# Headphone_Amplifier_Fixed.net
KiCad netlist of a schematic drawn in EAGLE
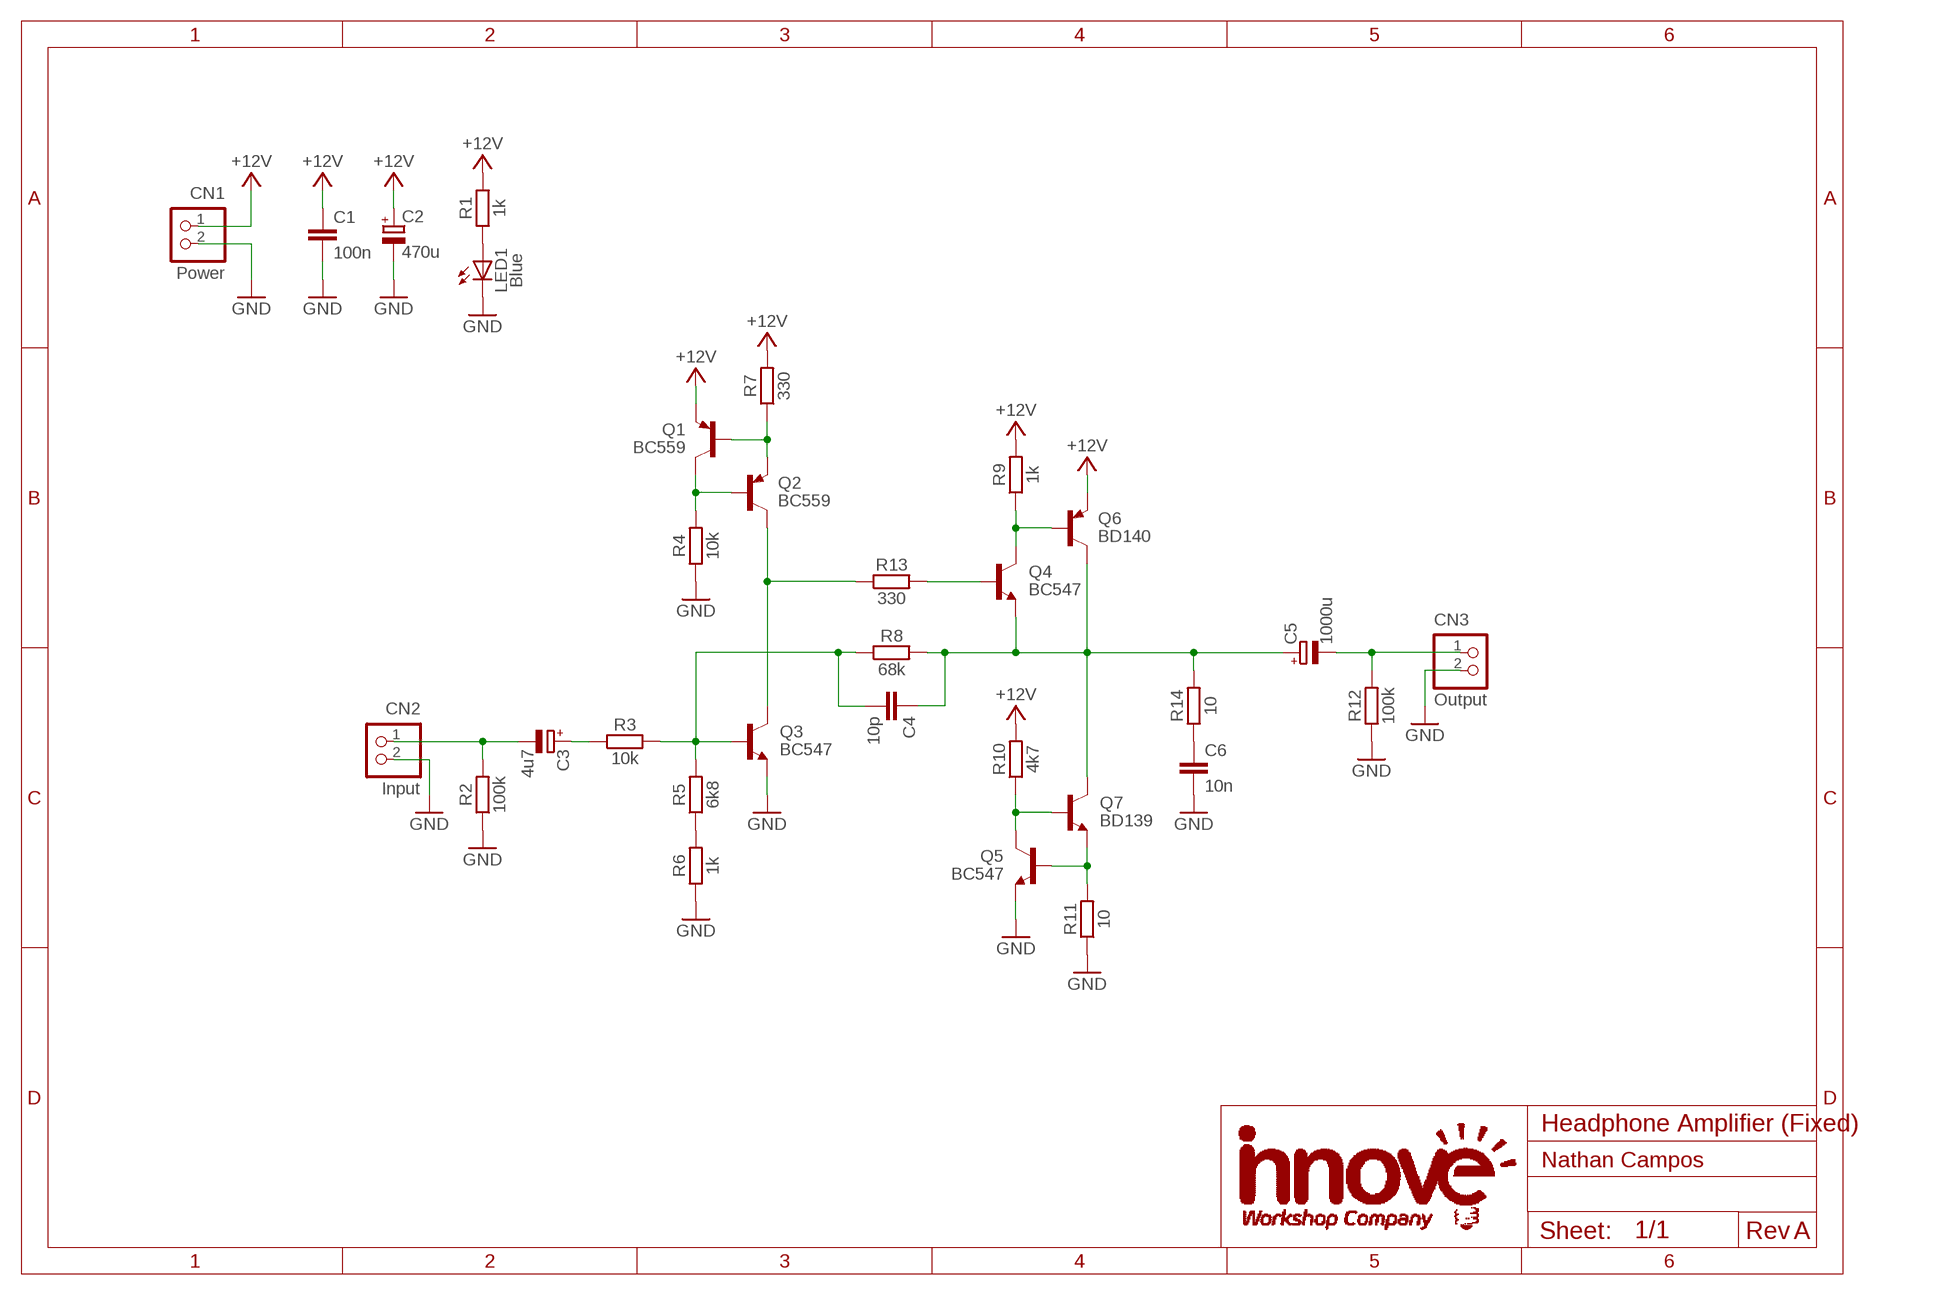
[diagram p0: schematic, sheet 1]

(export (version "E")
  (design (tool "Eeschema 10.0.6"))
  (components
    (comp (ref "C1")
      (value "100n")
      (footprint "eagle-import:C050-025X075")
      (libsource (lib "eagle-import") (part "C5.0-2.5X7.5"))
    )
    (comp (ref "C2")
      (value "470u")
      (footprint "eagle-import:E5-10")
      (libsource (lib "eagle-import") (part "CPOL-E5-10"))
    )
    (comp (ref "C3")
      (value "4u7")
      (footprint "eagle-import:E1,8-4")
      (libsource (lib "eagle-import") (part "CPOL-E1.8-4"))
    )
    (comp (ref "C4")
      (value "10p")
      (footprint "eagle-import:C050-025X075")
      (libsource (lib "eagle-import") (part "C5.0-2.5X7.5"))
    )
    (comp (ref "C5")
      (value "1000u")
      (footprint "eagle-import:E5-10")
      (libsource (lib "eagle-import") (part "CPOL-E5-10"))
    )
    (comp (ref "C6")
      (value "10n")
      (footprint "eagle-import:C050-025X075")
      (libsource (lib "eagle-import") (part "C5.0-2.5X7.5"))
    )
    (comp (ref "CN1")
      (value "Power")
      (footprint "eagle-import:B2B-XH-A")
      (libsource (lib "eagle-import") (part "B2B-XH-A"))
    )
    (comp (ref "CN2")
      (value "Input")
      (footprint "eagle-import:B2B-XH-A")
      (libsource (lib "eagle-import") (part "B2B-XH-A"))
    )
    (comp (ref "CN3")
      (value "Output")
      (footprint "eagle-import:B2B-XH-A")
      (libsource (lib "eagle-import") (part "B2B-XH-A"))
    )
    (comp (ref "LED1")
      (value "Blue")
      (footprint "eagle-import:LED5MM")
      (libsource (lib "eagle-import") (part "LED5MM"))
    )
    (comp (ref "Q1")
      (value "BC559")
      (footprint "eagle-import:TO92")
      (libsource (lib "eagle-import") (part "BC559"))
    )
    (comp (ref "Q2")
      (value "BC559")
      (footprint "eagle-import:TO92")
      (libsource (lib "eagle-import") (part "BC559"))
    )
    (comp (ref "Q3")
      (value "BC547")
      (footprint "eagle-import:TO92")
      (libsource (lib "eagle-import") (part "BC547"))
    )
    (comp (ref "Q4")
      (value "BC547")
      (footprint "eagle-import:TO92")
      (libsource (lib "eagle-import") (part "BC547"))
    )
    (comp (ref "Q5")
      (value "BC547")
      (footprint "eagle-import:TO92")
      (libsource (lib "eagle-import") (part "BC547"))
    )
    (comp (ref "Q6")
      (value "BD140")
      (footprint "eagle-import:TO126V")
      (libsource (lib "eagle-import") (part "BD140"))
    )
    (comp (ref "Q7")
      (value "BD139")
      (footprint "eagle-import:TO126V")
      (libsource (lib "eagle-import") (part "BD139"))
    )
    (comp (ref "R1")
      (value "1k")
      (footprint "eagle-import:0207_10")
      (libsource (lib "eagle-import") (part "RT0207"))
    )
    (comp (ref "R2")
      (value "100k")
      (footprint "eagle-import:0207_10")
      (libsource (lib "eagle-import") (part "RT0207"))
    )
    (comp (ref "R3")
      (value "10k")
      (footprint "eagle-import:0207_10")
      (libsource (lib "eagle-import") (part "RT0207"))
    )
    (comp (ref "R4")
      (value "10k")
      (footprint "eagle-import:0207_10")
      (libsource (lib "eagle-import") (part "RT0207"))
    )
    (comp (ref "R5")
      (value "6k8")
      (footprint "eagle-import:0207_10")
      (libsource (lib "eagle-import") (part "RT0207"))
    )
    (comp (ref "R6")
      (value "1k")
      (footprint "eagle-import:0207_10")
      (libsource (lib "eagle-import") (part "RT0207"))
    )
    (comp (ref "R7")
      (value "330")
      (footprint "eagle-import:0207_10")
      (libsource (lib "eagle-import") (part "RT0207"))
    )
    (comp (ref "R8")
      (value "68k")
      (footprint "eagle-import:0207_10")
      (libsource (lib "eagle-import") (part "RT0207"))
    )
    (comp (ref "R9")
      (value "1k")
      (footprint "eagle-import:0207_10")
      (libsource (lib "eagle-import") (part "RT0207"))
    )
    (comp (ref "R10")
      (value "4k7")
      (footprint "eagle-import:0207_10")
      (libsource (lib "eagle-import") (part "RT0207"))
    )
    (comp (ref "R11")
      (value "10")
      (footprint "eagle-import:0207_10")
      (libsource (lib "eagle-import") (part "RT0207"))
    )
    (comp (ref "R12")
      (value "100k")
      (footprint "eagle-import:0207_10")
      (libsource (lib "eagle-import") (part "RT0207"))
    )
    (comp (ref "R13")
      (value "330")
      (footprint "eagle-import:0207_10")
      (libsource (lib "eagle-import") (part "RT0207"))
    )
    (comp (ref "R14")
      (value "10")
      (footprint "eagle-import:0207_10")
      (libsource (lib "eagle-import") (part "RT0207"))
    )
  )
  (nets
    (net (code "1") (name "+12V") (class "Default")
      (node (ref "C1") (pin "1") (pinfunction "1_1") (pintype "passive"))
      (node (ref "C2") (pin "+") (pinfunction "+_+") (pintype "passive"))
      (node (ref "CN1") (pin "1") (pinfunction "1_1") (pintype "passive"))
      (node (ref "Q1") (pin "3") (pinfunction "E_3") (pintype "passive"))
      (node (ref "Q6") (pin "1") (pinfunction "E_1") (pintype "passive"))
      (node (ref "R1") (pin "2") (pinfunction "2_2") (pintype "passive"))
      (node (ref "R10") (pin "2") (pinfunction "2_2") (pintype "passive"))
      (node (ref "R7") (pin "2") (pinfunction "2_2") (pintype "passive"))
      (node (ref "R9") (pin "2") (pinfunction "2_2") (pintype "passive"))
    )
    (net (code "2") (name "GND") (class "Default")
      (node (ref "C1") (pin "2") (pinfunction "2_2") (pintype "passive"))
      (node (ref "C2") (pin "-") (pinfunction "-_-") (pintype "passive"))
      (node (ref "C6") (pin "2") (pinfunction "2_2") (pintype "passive"))
      (node (ref "CN1") (pin "2") (pinfunction "2_2") (pintype "passive"))
      (node (ref "CN2") (pin "2") (pinfunction "2_2") (pintype "passive"))
      (node (ref "CN3") (pin "2") (pinfunction "2_2") (pintype "passive"))
      (node (ref "LED1") (pin "K") (pinfunction "C_K") (pintype "passive"))
      (node (ref "Q3") (pin "3") (pinfunction "E_3") (pintype "passive"))
      (node (ref "Q5") (pin "3") (pinfunction "E_3") (pintype "passive"))
      (node (ref "R11") (pin "1") (pinfunction "1_1") (pintype "passive"))
      (node (ref "R12") (pin "1") (pinfunction "1_1") (pintype "passive"))
      (node (ref "R2") (pin "1") (pinfunction "1_1") (pintype "passive"))
      (node (ref "R4") (pin "1") (pinfunction "1_1") (pintype "passive"))
      (node (ref "R6") (pin "1") (pinfunction "1_1") (pintype "passive"))
    )
    (net (code "3") (name "Net-(C3-Pad+)") (class "Default")
      (node (ref "C3") (pin "+") (pinfunction "+_+") (pintype "passive"))
      (node (ref "R3") (pin "1") (pinfunction "1_1") (pintype "passive"))
    )
    (net (code "4") (name "Net-(C3-Pad-)") (class "Default")
      (node (ref "C3") (pin "-") (pinfunction "-_-") (pintype "passive"))
      (node (ref "CN2") (pin "1") (pinfunction "1_1") (pintype "passive"))
      (node (ref "R2") (pin "2") (pinfunction "2_2") (pintype "passive"))
    )
    (net (code "5") (name "Net-(C5-Pad-)") (class "Default")
      (node (ref "C5") (pin "-") (pinfunction "-_-") (pintype "passive"))
      (node (ref "CN3") (pin "1") (pinfunction "1_1") (pintype "passive"))
      (node (ref "R12") (pin "2") (pinfunction "2_2") (pintype "passive"))
    )
    (net (code "6") (name "Net-(C6-Pad1)") (class "Default")
      (node (ref "C6") (pin "1") (pinfunction "1_1") (pintype "passive"))
      (node (ref "R14") (pin "1") (pinfunction "1_1") (pintype "passive"))
    )
    (net (code "7") (name "Net-(LED1-PadA)") (class "Default")
      (node (ref "LED1") (pin "A") (pinfunction "A_A") (pintype "passive"))
      (node (ref "R1") (pin "1") (pinfunction "1_1") (pintype "passive"))
    )
    (net (code "8") (name "Net-(Q1-B)") (class "Default")
      (node (ref "Q1") (pin "2") (pinfunction "B_2") (pintype "passive"))
      (node (ref "Q2") (pin "3") (pinfunction "E_3") (pintype "passive"))
      (node (ref "R7") (pin "1") (pinfunction "1_1") (pintype "passive"))
    )
    (net (code "9") (name "Net-(Q1-C)") (class "Default")
      (node (ref "Q1") (pin "1") (pinfunction "C_1") (pintype "passive"))
      (node (ref "Q2") (pin "2") (pinfunction "B_2") (pintype "passive"))
      (node (ref "R4") (pin "2") (pinfunction "2_2") (pintype "passive"))
    )
    (net (code "10") (name "Net-(Q2-C)") (class "Default")
      (node (ref "Q2") (pin "1") (pinfunction "C_1") (pintype "passive"))
      (node (ref "Q3") (pin "1") (pinfunction "C_1") (pintype "passive"))
      (node (ref "R13") (pin "1") (pinfunction "1_1") (pintype "passive"))
    )
    (net (code "11") (name "Net-(Q3-B)") (class "Default")
      (node (ref "C4") (pin "2") (pinfunction "2_2") (pintype "passive"))
      (node (ref "Q3") (pin "2") (pinfunction "B_2") (pintype "passive"))
      (node (ref "R3") (pin "2") (pinfunction "2_2") (pintype "passive"))
      (node (ref "R5") (pin "2") (pinfunction "2_2") (pintype "passive"))
      (node (ref "R8") (pin "1") (pinfunction "1_1") (pintype "passive"))
    )
    (net (code "12") (name "Net-(Q4-B)") (class "Default")
      (node (ref "Q4") (pin "2") (pinfunction "B_2") (pintype "passive"))
      (node (ref "R13") (pin "2") (pinfunction "2_2") (pintype "passive"))
    )
    (net (code "13") (name "Net-(Q4-C)") (class "Default")
      (node (ref "Q4") (pin "1") (pinfunction "C_1") (pintype "passive"))
      (node (ref "Q6") (pin "3") (pinfunction "B_3") (pintype "passive"))
      (node (ref "R9") (pin "1") (pinfunction "1_1") (pintype "passive"))
    )
    (net (code "14") (name "Net-(Q4-E)") (class "Default")
      (node (ref "C4") (pin "1") (pinfunction "1_1") (pintype "passive"))
      (node (ref "C5") (pin "+") (pinfunction "+_+") (pintype "passive"))
      (node (ref "Q4") (pin "3") (pinfunction "E_3") (pintype "passive"))
      (node (ref "Q6") (pin "2") (pinfunction "C_2") (pintype "passive"))
      (node (ref "Q7") (pin "2") (pinfunction "C_2") (pintype "passive"))
      (node (ref "R14") (pin "2") (pinfunction "2_2") (pintype "passive"))
      (node (ref "R8") (pin "2") (pinfunction "2_2") (pintype "passive"))
    )
    (net (code "15") (name "Net-(Q5-B)") (class "Default")
      (node (ref "Q5") (pin "2") (pinfunction "B_2") (pintype "passive"))
      (node (ref "Q7") (pin "1") (pinfunction "E_1") (pintype "passive"))
      (node (ref "R11") (pin "2") (pinfunction "2_2") (pintype "passive"))
    )
    (net (code "16") (name "Net-(Q5-C)") (class "Default")
      (node (ref "Q5") (pin "1") (pinfunction "C_1") (pintype "passive"))
      (node (ref "Q7") (pin "3") (pinfunction "B_3") (pintype "passive"))
      (node (ref "R10") (pin "1") (pinfunction "1_1") (pintype "passive"))
    )
    (net (code "17") (name "Net-(R5-Pad1)") (class "Default")
      (node (ref "R5") (pin "1") (pinfunction "1_1") (pintype "passive"))
      (node (ref "R6") (pin "2") (pinfunction "2_2") (pintype "passive"))
    )
  )
)
